# 1S-Bat-Charger.net
KiCad netlist of a schematic drawn in EasyEDA Pro
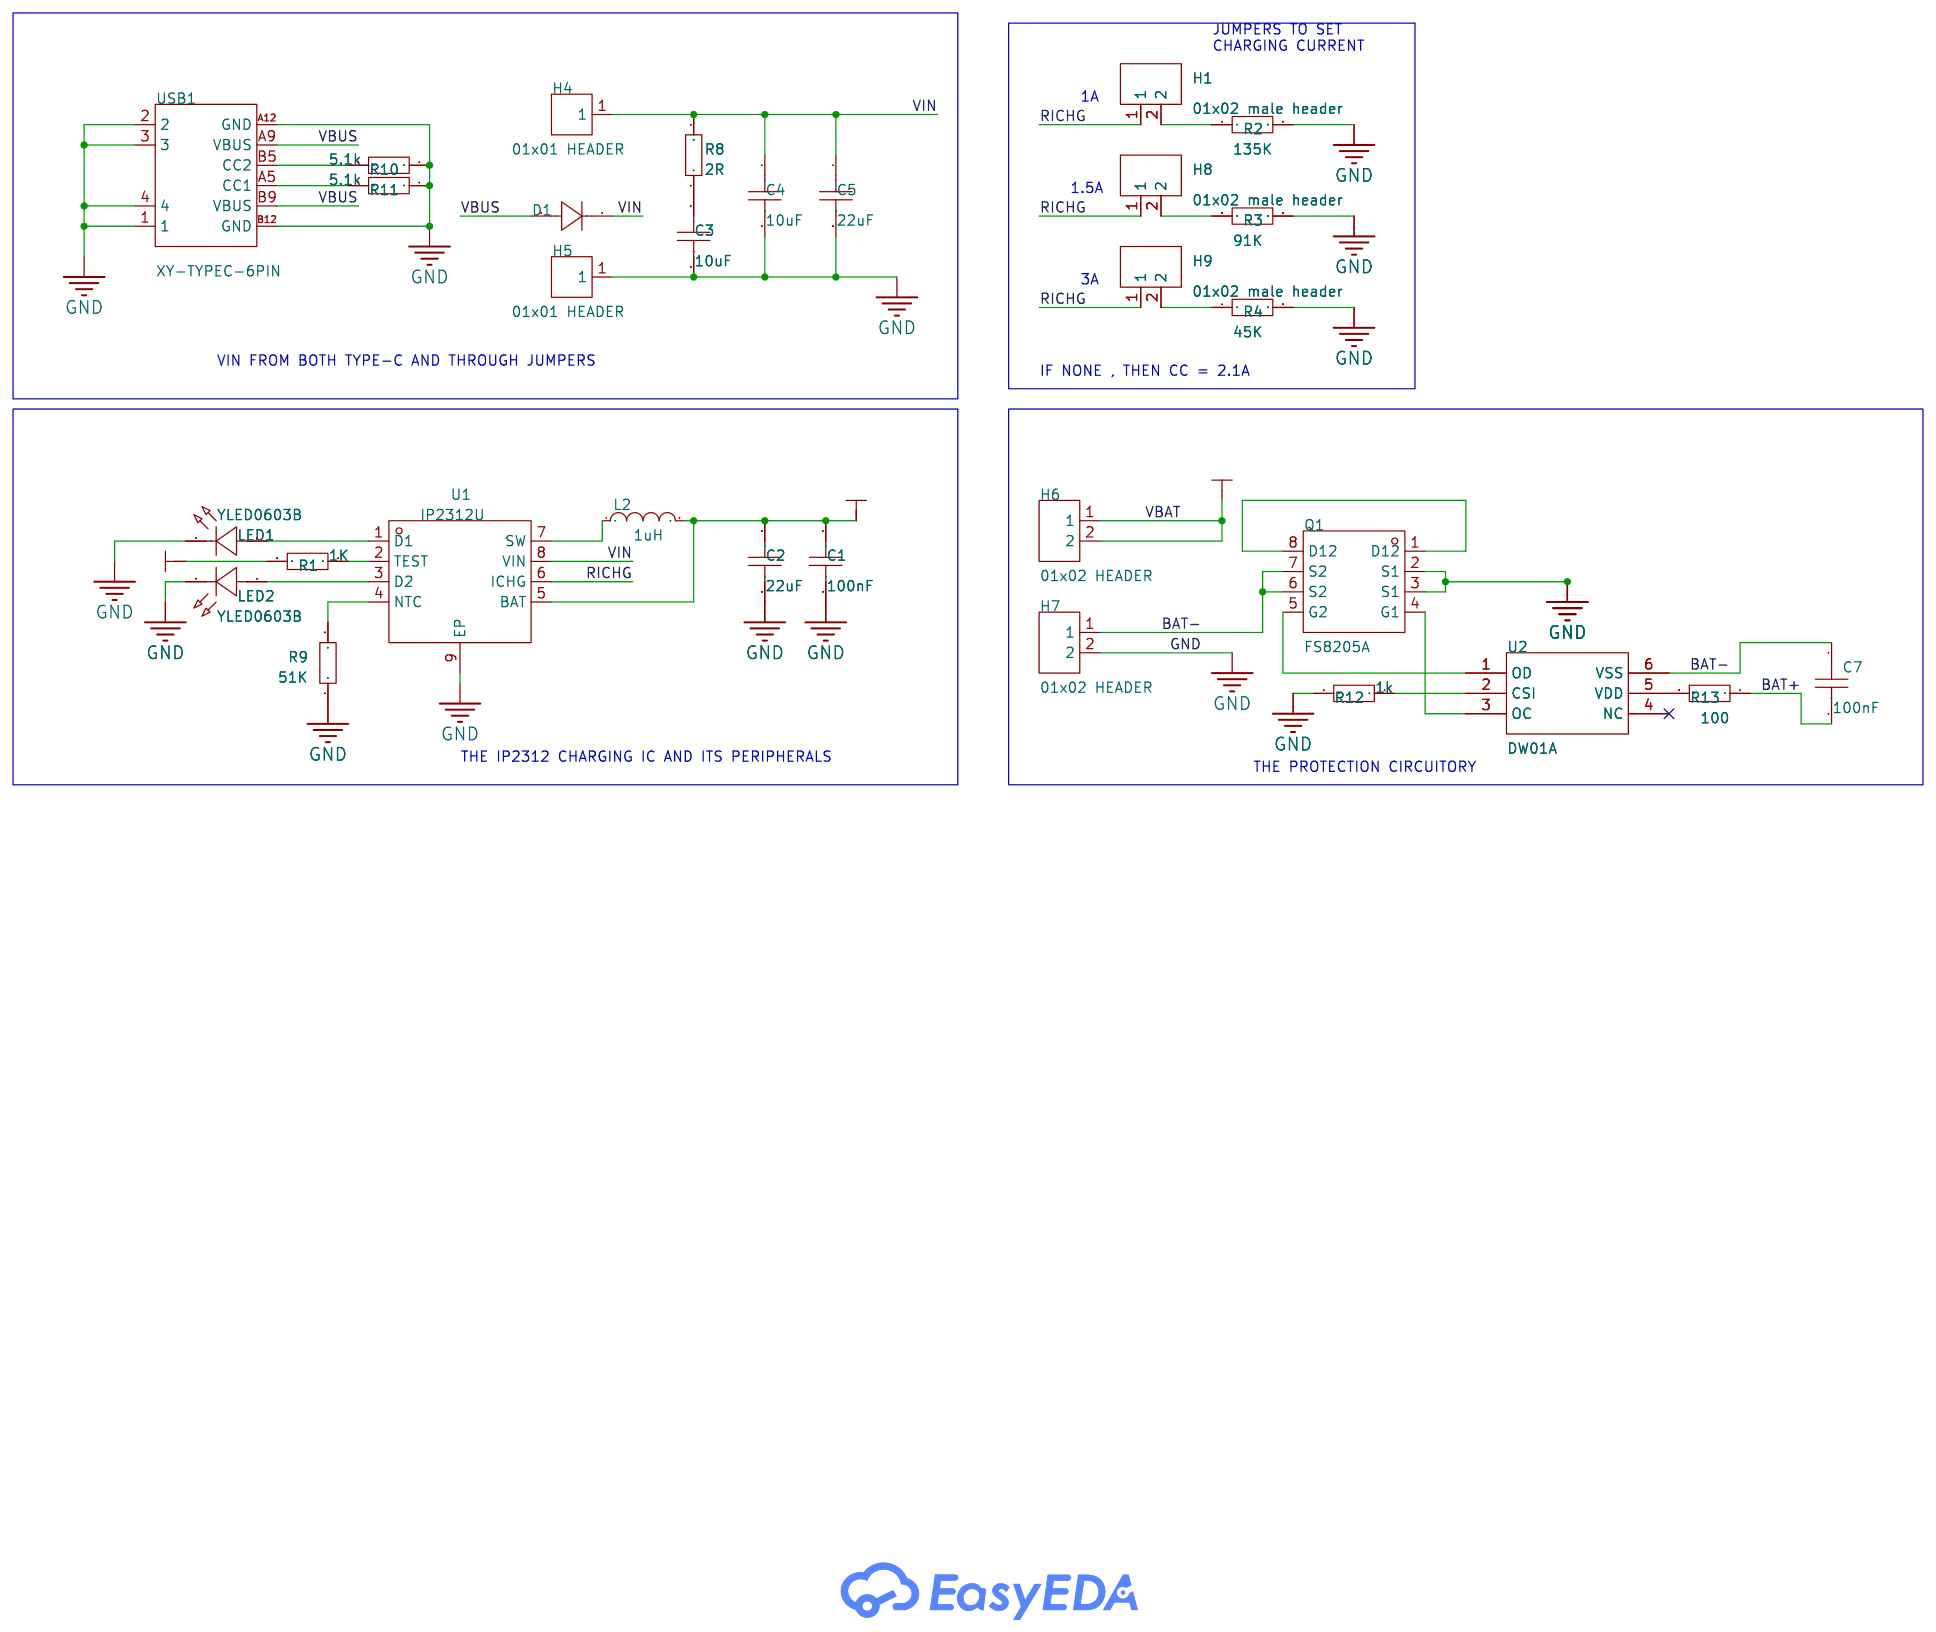
[diagram p0: schematic sheet]

(export (version "E")
  (design (tool "Eeschema 10.0.6"))
  (components
    (comp (ref "C1")
      (value "100nF")
      (footprint "easyedapro:C0603")
      (libsource (lib "easyedapro") (part "CAP"))
    )
    (comp (ref "C2")
      (value "22uF")
      (footprint "easyedapro:C0603")
      (libsource (lib "easyedapro") (part "CAP"))
    )
    (comp (ref "C3")
      (value "10uF")
      (footprint "easyedapro:C0603")
      (libsource (lib "easyedapro") (part "CAP"))
    )
    (comp (ref "C4")
      (value "10uF")
      (footprint "easyedapro:C0603")
      (libsource (lib "easyedapro") (part "CAP"))
    )
    (comp (ref "C5")
      (value "22uF")
      (footprint "easyedapro:C0603")
      (libsource (lib "easyedapro") (part "CAP"))
    )
    (comp (ref "C7")
      (value "100nF")
      (footprint "easyedapro:C0603")
      (libsource (lib "easyedapro") (part "CAP"))
    )
    (comp (ref "D1")
      (value "~")
      (footprint "easyedapro:SMA_L4.4-W2.8-LS5.4-RD")
      (libsource (lib "easyedapro") (part "D_1N4007"))
    )
    (comp (ref "H1")
      (value "01x02 male header")
      (footprint "easyedapro:HDR-TH_2P-P2.54-V-M")
      (fields (field (name "Manufacturer") "hanxia(韩下)"))
      (libsource (lib "easyedapro") (part "HX PH254-01-02-Z-L11.5 MALE HEADER CONNECTOR"))
    )
    (comp (ref "H4")
      (value "01x01 HEADER")
      (footprint "easyedapro:HDR-TH_1P-P2.54-V-M")
      (fields (field (name "Manufacturer") "JXTCONN(聚兴泰)"))
      (libsource (lib "easyedapro") (part "PH2.54-1X1P-H25"))
    )
    (comp (ref "H5")
      (value "01x01 HEADER")
      (footprint "easyedapro:HDR-TH_1P-P2.54-V-M")
      (fields (field (name "Manufacturer") "JXTCONN(聚兴泰)"))
      (libsource (lib "easyedapro") (part "PH2.54-1X1P-H25"))
    )
    (comp (ref "H6")
      (value "01x02 HEADER")
      (footprint "easyedapro:HDR-TH_2P-P2.54-V-M")
      (fields (field (name "Manufacturer") "hanxia(韩下)"))
      (libsource (lib "easyedapro") (part "HX PH254-01-02-Z-L11.5 MALE HEADER CONNECTOR"))
    )
    (comp (ref "H7")
      (value "01x02 HEADER")
      (footprint "easyedapro:HDR-TH_2P-P2.54-V-M")
      (fields (field (name "Manufacturer") "hanxia(韩下)"))
      (libsource (lib "easyedapro") (part "HX PH254-01-02-Z-L11.5 MALE HEADER CONNECTOR"))
    )
    (comp (ref "H8")
      (value "01x02 male header")
      (footprint "easyedapro:HDR-TH_2P-P2.54-V-M")
      (fields (field (name "Manufacturer") "hanxia(韩下)"))
      (libsource (lib "easyedapro") (part "HX PH254-01-02-Z-L11.5 MALE HEADER CONNECTOR"))
    )
    (comp (ref "H9")
      (value "01x02 male header")
      (footprint "easyedapro:HDR-TH_2P-P2.54-V-M")
      (fields (field (name "Manufacturer") "hanxia(韩下)"))
      (libsource (lib "easyedapro") (part "HX PH254-01-02-Z-L11.5 MALE HEADER CONNECTOR"))
    )
    (comp (ref "L2")
      (value "1uH")
      (footprint "easyedapro:IND-SMD_L4.4-W4.2")
      (fields (field (name "Manufacturer Part") "APH0420T1R0M") (field (name "Manufacturer") "APV(爱普微)"))
      (libsource (lib "easyedapro") (part "APH0420T1R0M"))
    )
    (comp (ref "LED1")
      (value "YLED0603B")
      (footprint "easyedapro:LED0603-FD")
      (fields (field (name "Manufacturer") "YONGYUTAI(永裕泰)"))
      (libsource (lib "easyedapro") (part "YLED0603B"))
    )
    (comp (ref "LED2")
      (value "YLED0603B")
      (footprint "easyedapro:LED0603-FD")
      (fields (field (name "Manufacturer") "YONGYUTAI(永裕泰)"))
      (libsource (lib "easyedapro") (part "YLED0603B"))
    )
    (comp (ref "Q1")
      (value "FS8205A")
      (footprint "easyedapro:TSSOP-8_L4.4-W3.0-P0.65-LS6.4-BL-2")
      (fields (field (name "Manufacturer") "FORTUNE(富晶)"))
      (libsource (lib "easyedapro") (part "FS8205A"))
    )
    (comp (ref "R1") (value "1K") (footprint "easyedapro:R0603") (libsource (lib "easyedapro") (part "Res")))
    (comp (ref "R2")
      (value "135K")
      (footprint "easyedapro:R0603")
      (libsource (lib "easyedapro") (part "Res"))
    )
    (comp (ref "R3") (value "91K") (footprint "easyedapro:R0603") (libsource (lib "easyedapro") (part "Res")))
    (comp (ref "R4") (value "45K") (footprint "easyedapro:R0603") (libsource (lib "easyedapro") (part "Res")))
    (comp (ref "R8") (value "2R") (footprint "easyedapro:R0603") (libsource (lib "easyedapro") (part "Res")))
    (comp (ref "R9") (value "51K") (footprint "easyedapro:R0603") (libsource (lib "easyedapro") (part "Res")))
    (comp (ref "R10")
      (value "5.1k")
      (footprint "easyedapro:R0603")
      (libsource (lib "easyedapro") (part "Res"))
    )
    (comp (ref "R11")
      (value "5.1k")
      (footprint "easyedapro:R0603")
      (libsource (lib "easyedapro") (part "Res"))
    )
    (comp (ref "R12") (value "1k") (footprint "easyedapro:R0603") (libsource (lib "easyedapro") (part "Res")))
    (comp (ref "R13")
      (value "100")
      (footprint "easyedapro:R0603")
      (libsource (lib "easyedapro") (part "Res"))
    )
    (comp (ref "U1")
      (value "IP2312U")
      (footprint "easyedapro:ESOP-8_L4.9-W3.9-P1.27-LS6.0-BL-EP")
      (fields (field (name "Manufacturer") "INJOINIC(英集芯)"))
      (libsource (lib "easyedapro") (part "IP2312U"))
    )
    (comp (ref "U2")
      (value "DW01A")
      (footprint "easyedapro:SOT-23-6_L2.9-W1.6-P0.95-LS2.8-BL")
      (fields (field (name "Manufacturer") "KUU"))
      (libsource (lib "easyedapro") (part "DW01A_C42459937"))
    )
    (comp (ref "USB1")
      (value "XY-TYPEC-6PIN")
      (footprint "easyedapro:USB-C-SMD_XY-TYPEC-6PIN")
      (fields (field (name "Manufacturer") "XYECONN(辛译)"))
      (libsource (lib "easyedapro") (part "XY-TYPEC-6PIN"))
    )
  )
  (nets
    (net (code "1") (name "/BAT+") (class "Default")
      (node (ref "C7") (pin "2") (pinfunction "2_2") (pintype "input"))
      (node (ref "R13") (pin "1") (pinfunction "1_1") (pintype "input"))
    )
    (net (code "2") (name "/BAT-") (class "Default")
      (node (ref "C7") (pin "1") (pinfunction "1_1") (pintype "input"))
      (node (ref "H7") (pin "1") (pinfunction "1_1") (pintype "unspecified"))
      (node (ref "Q1") (pin "6") (pinfunction "S2_6") (pintype "unspecified"))
      (node (ref "Q1") (pin "7") (pinfunction "S2_7") (pintype "unspecified"))
      (node (ref "U2") (pin "6") (pinfunction "VSS_6") (pintype "unspecified"))
    )
    (net (code "3") (name "/RICHG") (class "Default")
      (node (ref "H1") (pin "1") (pinfunction "1_1") (pintype "unspecified"))
      (node (ref "H8") (pin "1") (pinfunction "1_1") (pintype "unspecified"))
      (node (ref "H9") (pin "1") (pinfunction "1_1") (pintype "unspecified"))
      (node (ref "U1") (pin "6") (pinfunction "ICHG_6") (pintype "unspecified"))
    )
    (net (code "4") (name "/VBUS") (class "Default")
      (node (ref "D1") (pin "2") (pinfunction "A_2") (pintype "input"))
      (node (ref "USB1") (pin "A9") (pinfunction "VBUS_A9") (pintype "unspecified"))
      (node (ref "USB1") (pin "B9") (pinfunction "VBUS_B9") (pintype "unspecified"))
    )
    (net (code "5") (name "/VIN") (class "Default")
      (node (ref "C4") (pin "1") (pinfunction "1_1") (pintype "input"))
      (node (ref "C5") (pin "1") (pinfunction "1_1") (pintype "input"))
      (node (ref "D1") (pin "1") (pinfunction "K_1") (pintype "input"))
      (node (ref "H4") (pin "1") (pinfunction "1_1") (pintype "unspecified"))
      (node (ref "R8") (pin "2") (pinfunction "2_2") (pintype "input"))
      (node (ref "U1") (pin "8") (pinfunction "VIN_8") (pintype "unspecified"))
    )
    (net (code "6") (name "GND") (class "Default")
      (node (ref "C1") (pin "2") (pinfunction "2_2") (pintype "input"))
      (node (ref "C2") (pin "2") (pinfunction "2_2") (pintype "input"))
      (node (ref "C3") (pin "2") (pinfunction "2_2") (pintype "input"))
      (node (ref "C4") (pin "2") (pinfunction "2_2") (pintype "input"))
      (node (ref "C5") (pin "2") (pinfunction "2_2") (pintype "input"))
      (node (ref "H5") (pin "1") (pinfunction "1_1") (pintype "unspecified"))
      (node (ref "H7") (pin "2") (pinfunction "2_2") (pintype "unspecified"))
      (node (ref "LED1") (pin "1") (pinfunction "K_1") (pintype "unspecified"))
      (node (ref "LED2") (pin "1") (pinfunction "K_1") (pintype "unspecified"))
      (node (ref "Q1") (pin "2") (pinfunction "S1_2") (pintype "unspecified"))
      (node (ref "Q1") (pin "3") (pinfunction "S1_3") (pintype "unspecified"))
      (node (ref "R10") (pin "1") (pinfunction "1_1") (pintype "input"))
      (node (ref "R11") (pin "1") (pinfunction "1_1") (pintype "input"))
      (node (ref "R12") (pin "2") (pinfunction "2_2") (pintype "input"))
      (node (ref "R2") (pin "2") (pinfunction "2_2") (pintype "input"))
      (node (ref "R3") (pin "2") (pinfunction "2_2") (pintype "input"))
      (node (ref "R4") (pin "2") (pinfunction "2_2") (pintype "input"))
      (node (ref "R9") (pin "1") (pinfunction "1_1") (pintype "input"))
      (node (ref "U1") (pin "9") (pinfunction "EP_9") (pintype "unspecified"))
      (node (ref "USB1") (pin "1") (pinfunction "1_1") (pintype "unspecified"))
      (node (ref "USB1") (pin "2") (pinfunction "2_2") (pintype "unspecified"))
      (node (ref "USB1") (pin "3") (pinfunction "3_3") (pintype "unspecified"))
      (node (ref "USB1") (pin "4") (pinfunction "4_4") (pintype "unspecified"))
      (node (ref "USB1") (pin "A12") (pinfunction "GND_A12") (pintype "unspecified"))
      (node (ref "USB1") (pin "B12") (pinfunction "GND_B12") (pintype "unspecified"))
    )
    (net (code "7") (name "Net-(C3-Pad1)") (class "Default")
      (node (ref "C3") (pin "1") (pinfunction "1_1") (pintype "input"))
      (node (ref "R8") (pin "1") (pinfunction "1_1") (pintype "input"))
    )
    (net (code "8") (name "Net-(H1-Pad2)") (class "Default")
      (node (ref "H1") (pin "2") (pinfunction "2_2") (pintype "unspecified"))
      (node (ref "R2") (pin "1") (pinfunction "1_1") (pintype "input"))
    )
    (net (code "9") (name "Net-(H8-Pad2)") (class "Default")
      (node (ref "H8") (pin "2") (pinfunction "2_2") (pintype "unspecified"))
      (node (ref "R3") (pin "1") (pinfunction "1_1") (pintype "input"))
    )
    (net (code "10") (name "Net-(H9-Pad2)") (class "Default")
      (node (ref "H9") (pin "2") (pinfunction "2_2") (pintype "unspecified"))
      (node (ref "R4") (pin "1") (pinfunction "1_1") (pintype "input"))
    )
    (net (code "11") (name "Net-(LED1-A)") (class "Default")
      (node (ref "LED1") (pin "2") (pinfunction "A_2") (pintype "unspecified"))
      (node (ref "U1") (pin "1") (pinfunction "D1_1") (pintype "unspecified"))
    )
    (net (code "12") (name "Net-(LED2-A)") (class "Default")
      (node (ref "LED2") (pin "2") (pinfunction "A_2") (pintype "unspecified"))
      (node (ref "U1") (pin "3") (pinfunction "D2_3") (pintype "unspecified"))
    )
    (net (code "13") (name "Net-(Q1-D12-Pad1)") (class "Default")
      (node (ref "Q1") (pin "1") (pinfunction "D12_1") (pintype "unspecified"))
      (node (ref "Q1") (pin "8") (pinfunction "D12_8") (pintype "unspecified"))
    )
    (net (code "14") (name "Net-(Q1-G1)") (class "Default")
      (node (ref "Q1") (pin "4") (pinfunction "G1_4") (pintype "unspecified"))
      (node (ref "U2") (pin "3") (pinfunction "OC_3") (pintype "unspecified"))
    )
    (net (code "15") (name "Net-(Q1-G2)") (class "Default")
      (node (ref "Q1") (pin "5") (pinfunction "G2_5") (pintype "unspecified"))
      (node (ref "U2") (pin "1") (pinfunction "OD_1") (pintype "unspecified"))
    )
    (net (code "16") (name "Net-(U1-NTC)") (class "Default")
      (node (ref "R9") (pin "2") (pinfunction "2_2") (pintype "input"))
      (node (ref "U1") (pin "4") (pinfunction "NTC_4") (pintype "unspecified"))
    )
    (net (code "17") (name "Net-(U1-SW)") (class "Default")
      (node (ref "L2") (pin "1") (pinfunction "1_1") (pintype "unspecified"))
      (node (ref "U1") (pin "7") (pinfunction "SW_7") (pintype "unspecified"))
    )
    (net (code "18") (name "Net-(U1-TEST)") (class "Default")
      (node (ref "R1") (pin "1") (pinfunction "1_1") (pintype "input"))
      (node (ref "U1") (pin "2") (pinfunction "TEST_2") (pintype "unspecified"))
    )
    (net (code "19") (name "Net-(U2-CSI)") (class "Default")
      (node (ref "R12") (pin "1") (pinfunction "1_1") (pintype "input"))
      (node (ref "U2") (pin "2") (pinfunction "CSI_2") (pintype "unspecified"))
    )
    (net (code "20") (name "Net-(U2-VDD)") (class "Default")
      (node (ref "R13") (pin "2") (pinfunction "2_2") (pintype "input"))
      (node (ref "U2") (pin "5") (pinfunction "VDD_5") (pintype "unspecified"))
    )
    (net (code "21") (name "Net-(USB1-CC1)") (class "Default")
      (node (ref "R11") (pin "2") (pinfunction "2_2") (pintype "input"))
      (node (ref "USB1") (pin "A5") (pinfunction "CC1_A5") (pintype "unspecified"))
    )
    (net (code "22") (name "Net-(USB1-CC2)") (class "Default")
      (node (ref "R10") (pin "2") (pinfunction "2_2") (pintype "input"))
      (node (ref "USB1") (pin "B5") (pinfunction "CC2_B5") (pintype "unspecified"))
    )
    (net (code "23") (name "VBAT") (class "Default")
      (node (ref "C1") (pin "1") (pinfunction "1_1") (pintype "input"))
      (node (ref "C2") (pin "1") (pinfunction "1_1") (pintype "input"))
      (node (ref "H6") (pin "1") (pinfunction "1_1") (pintype "unspecified"))
      (node (ref "H6") (pin "2") (pinfunction "2_2") (pintype "unspecified"))
      (node (ref "L2") (pin "2") (pinfunction "2_2") (pintype "unspecified"))
      (node (ref "R1") (pin "2") (pinfunction "2_2") (pintype "input"))
      (node (ref "U1") (pin "5") (pinfunction "BAT_5") (pintype "unspecified"))
    )
    (net (code "24") (name "unconnected-(U2-NC-Pad4)") (class "Default")
      (node (ref "U2") (pin "4") (pinfunction "NC_4") (pintype "unspecified+no_connect"))
    )
  )
)
